# fp_usb.net
KiCad netlist of a schematic drawn in EAGLE
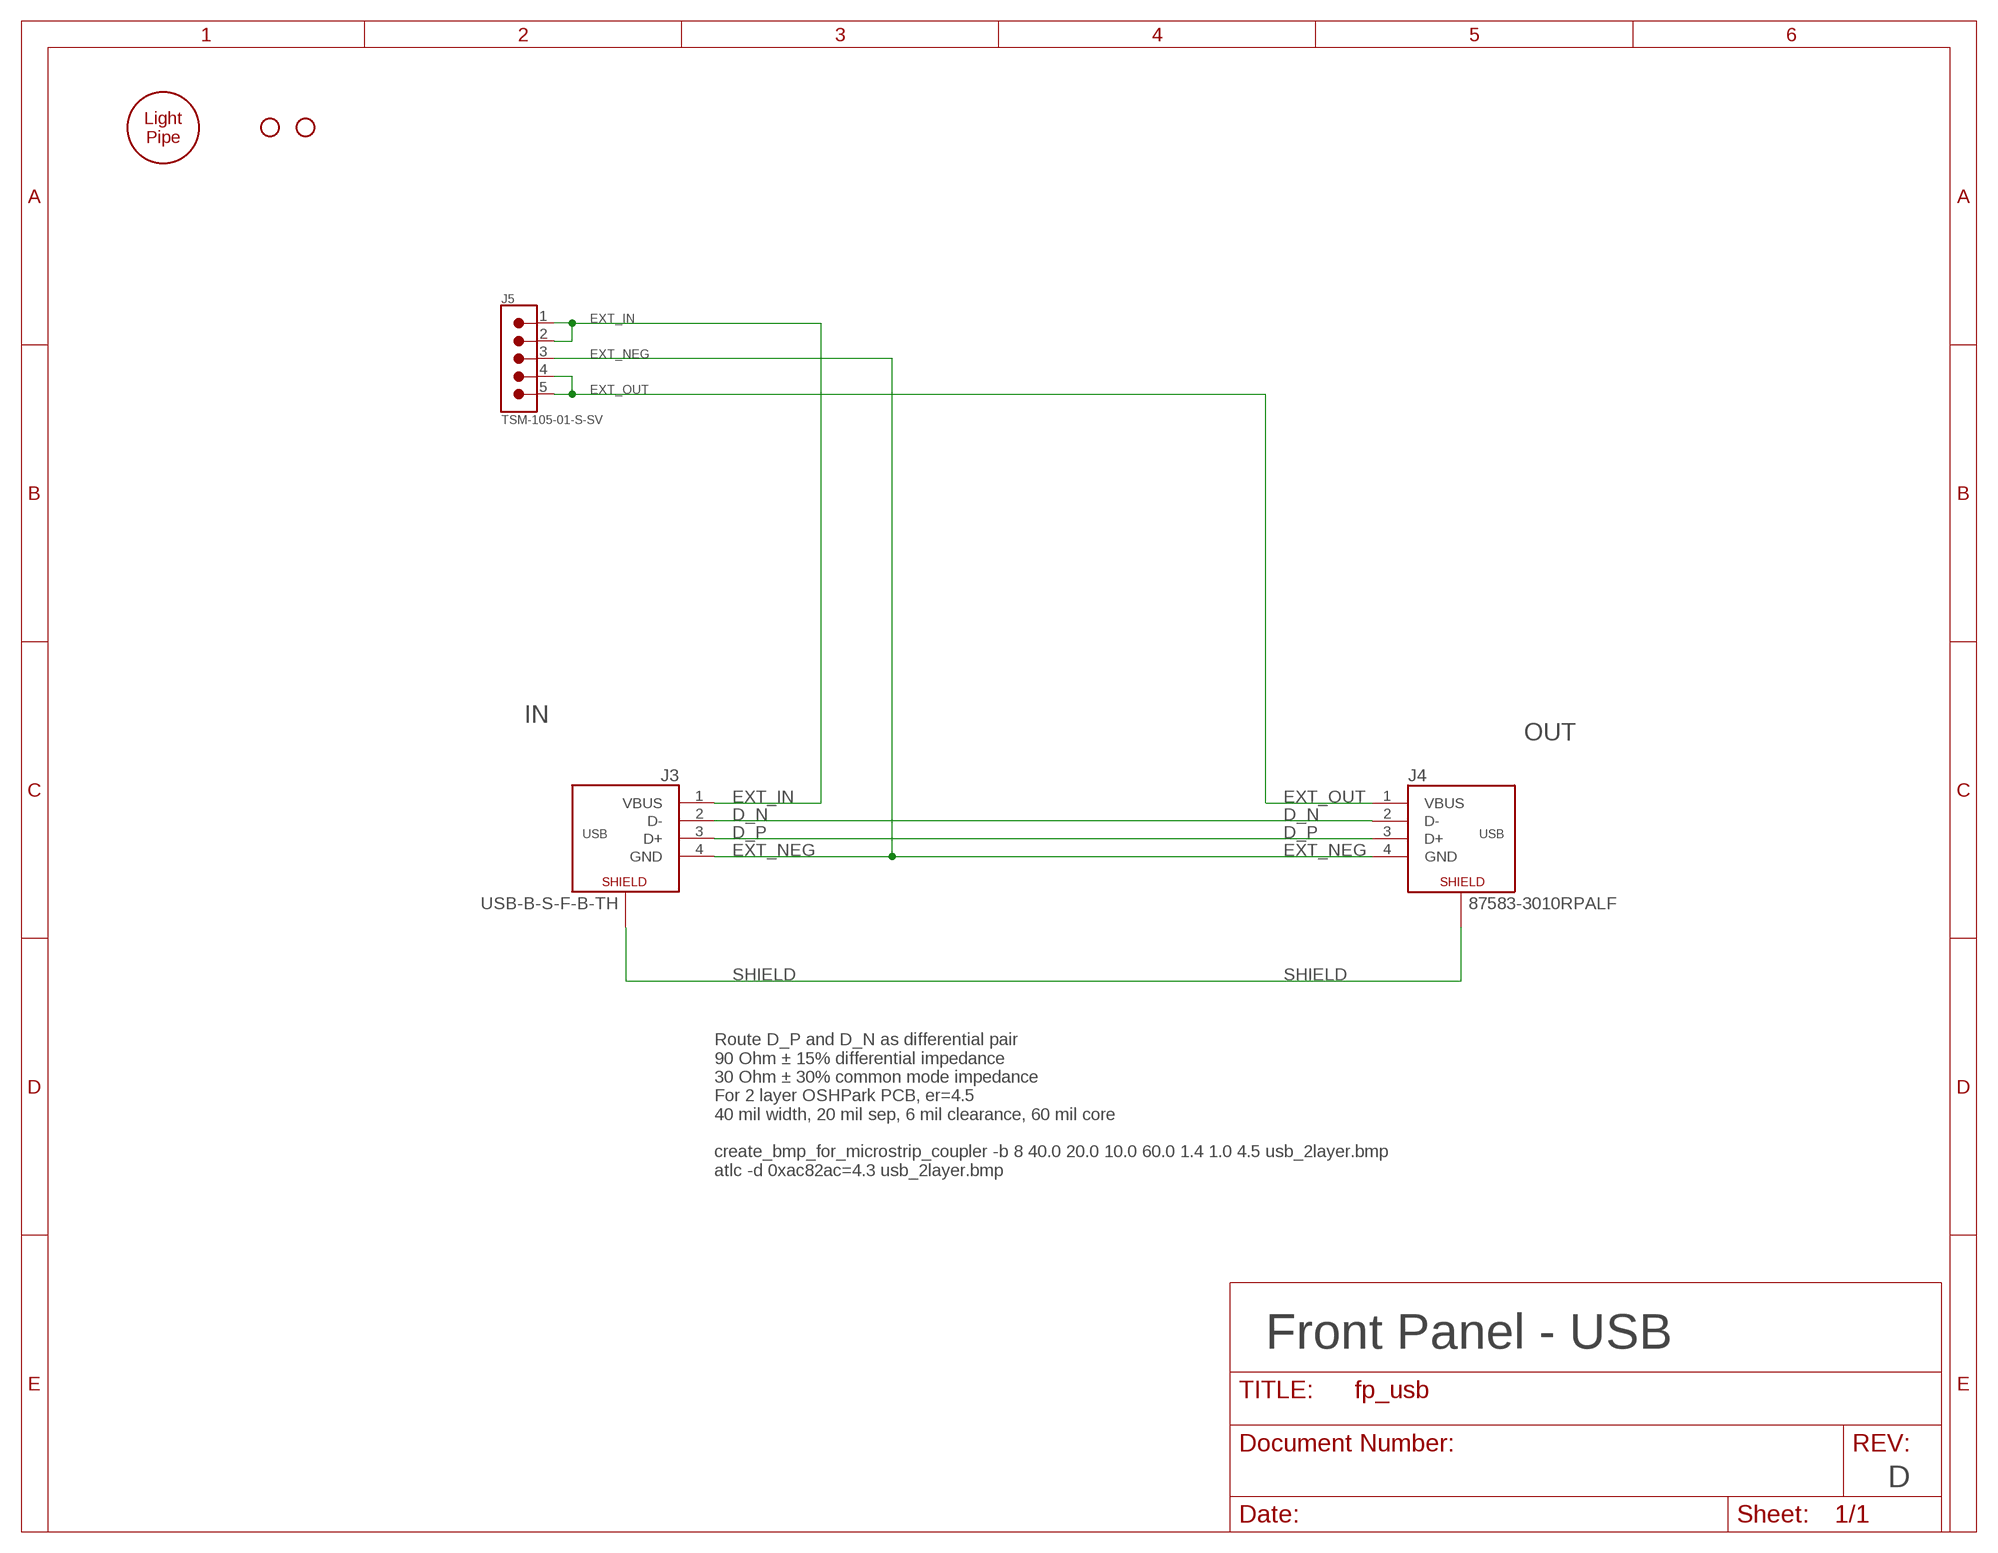
[diagram p0: schematic, sheet 1]

(export (version "E")
  (design (tool "Eeschema 10.0.6"))
  (components
    (comp (ref "H1")
      (value "51513020125F")
      (footprint "eagle-import:LP_3MM")
      (fields (field (name "MPN") "51513020125F"))
      (libsource (lib "eagle-import") (part "LIGHT_PIPE_PANEL_3MM"))
    )
    (comp (ref "H3")
      (value "HOLE_#6")
      (footprint "eagle-import:HOLE_3.5MM")
      (libsource (lib "eagle-import") (part "HOLE_#6"))
    )
    (comp (ref "H4")
      (value "HOLE_#6")
      (footprint "eagle-import:HOLE_3.5MM")
      (libsource (lib "eagle-import") (part "HOLE_#6"))
    )
    (comp (ref "J3")
      (value "USB-B-S-F-B-TH")
      (footprint "eagle-import:USB-B-TH")
      (libsource (lib "eagle-import") (part "USB-4_B-TH"))
    )
    (comp (ref "J4")
      (value "87583-3010RPALF")
      (footprint "eagle-import:USB-A_RPCT")
      (libsource (lib "eagle-import") (part "USB-4-A_RCPT"))
    )
    (comp (ref "J5")
      (value "TSM-105-01-S-SV")
      (footprint "eagle-import:CONN_0.1_5X1_MS")
      (libsource (lib "eagle-import") (part "CONN_0.1_5X1_MS"))
    )
  )
  (nets
    (net (code "1") (name "/D_N") (class "Default")
      (node (ref "J3") (pin "2") (pinfunction "D-_2") (pintype "bidirectional"))
      (node (ref "J4") (pin "2") (pinfunction "D-_2") (pintype "bidirectional"))
    )
    (net (code "2") (name "/D_P") (class "Default")
      (node (ref "J3") (pin "3") (pinfunction "D+_3") (pintype "bidirectional"))
      (node (ref "J4") (pin "3") (pinfunction "D+_3") (pintype "bidirectional"))
    )
    (net (code "3") (name "/EXT_IN") (class "Default")
      (node (ref "J3") (pin "1") (pinfunction "VBUS_1") (pintype "bidirectional"))
      (node (ref "J5") (pin "1") (pinfunction "1_1") (pintype "bidirectional"))
      (node (ref "J5") (pin "2") (pinfunction "2_2") (pintype "bidirectional"))
    )
    (net (code "4") (name "/EXT_NEG") (class "Default")
      (node (ref "J3") (pin "4") (pinfunction "GND_4") (pintype "bidirectional"))
      (node (ref "J4") (pin "4") (pinfunction "GND_4") (pintype "bidirectional"))
      (node (ref "J5") (pin "3") (pinfunction "3_3") (pintype "bidirectional"))
    )
    (net (code "5") (name "/EXT_OUT") (class "Default")
      (node (ref "J4") (pin "1") (pinfunction "VBUS_1") (pintype "bidirectional"))
      (node (ref "J5") (pin "4") (pinfunction "4_4") (pintype "bidirectional"))
      (node (ref "J5") (pin "5") (pinfunction "5_5") (pintype "bidirectional"))
    )
    (net (code "6") (name "/SHIELD") (class "Default")
      (node (ref "J3") (pin "SHIELD@1") (pinfunction "SHIELD_SHIELD@1") (pintype "bidirectional"))
      (node (ref "J3") (pin "SHIELD@2") (pinfunction "SHIELD_SHIELD@2") (pintype "bidirectional"))
      (node (ref "J4") (pin "SHIELD@1") (pinfunction "SHIELD_SHIELD@1") (pintype "bidirectional"))
      (node (ref "J4") (pin "SHIELD@2") (pinfunction "SHIELD_SHIELD@2") (pintype "bidirectional"))
    )
  )
)
